# Power_supply.net
KiCad netlist of a schematic drawn in Altium Designer
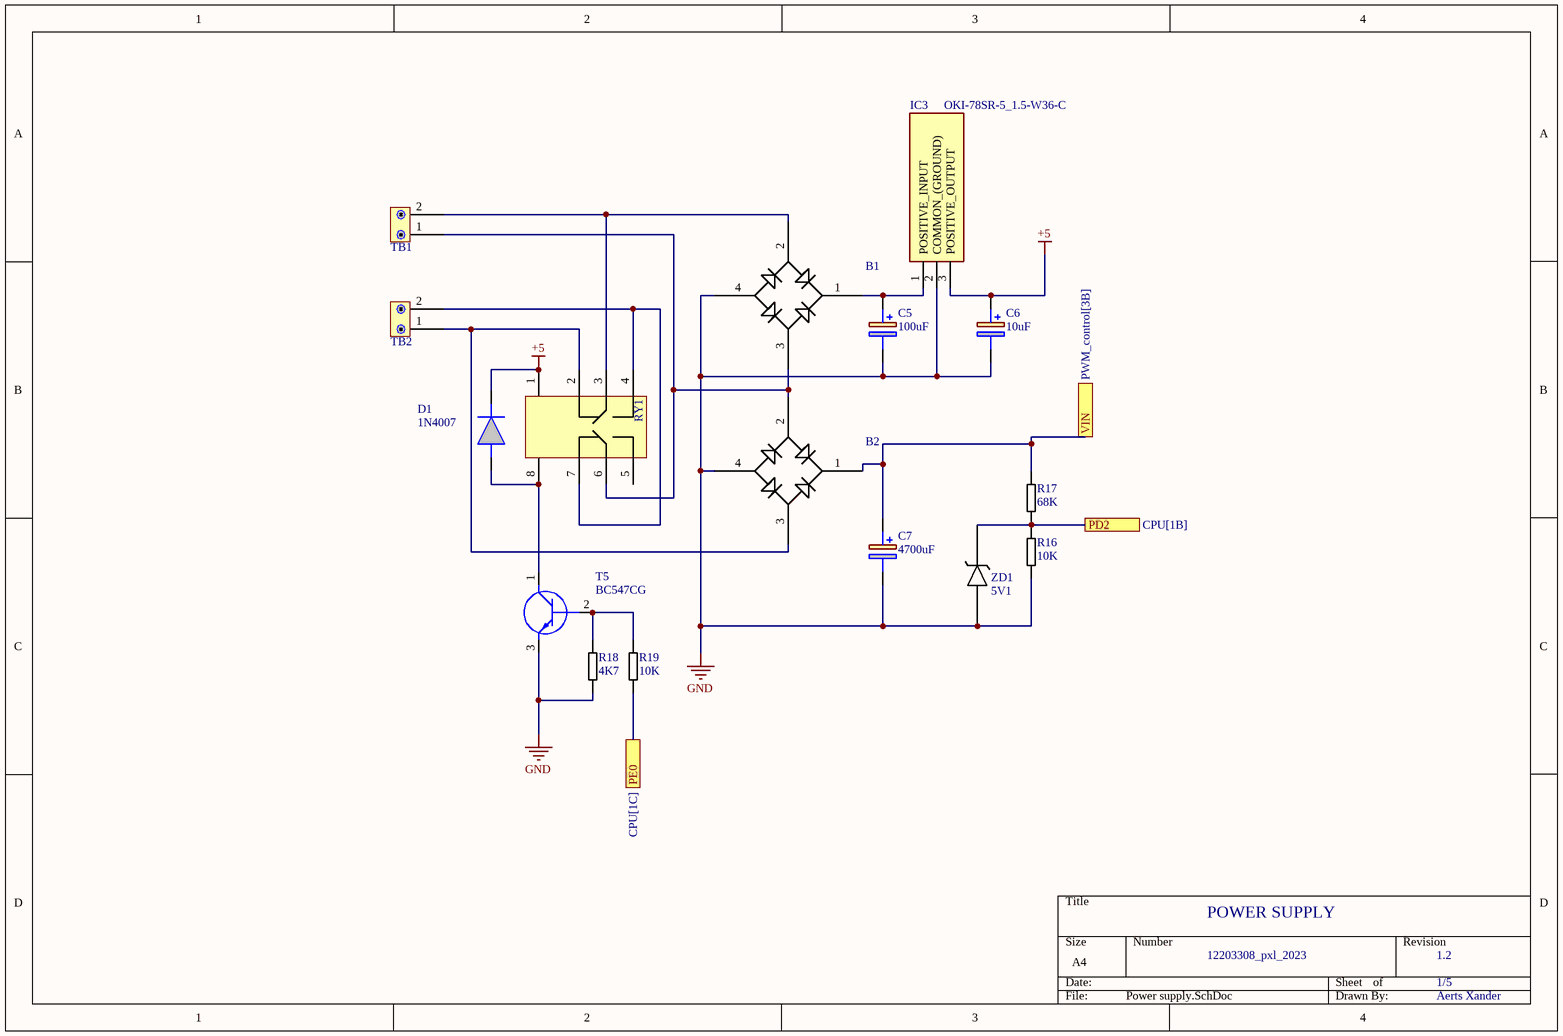
[diagram p0: Power supply.SchDoc]

(export (version "E")
  (design (tool "Eeschema 10.0.6"))
  (components
    (comp (ref "B1")
      (value "Bruggelijkrichter")
      (footprint "Bruggelijkrichter")
      (libsource (lib "soldeerstation") (part "Bruggelijkrichter"))
    )
    (comp (ref "B2")
      (value "Bruggelijkrichter")
      (footprint "Bruggelijkrichter")
      (libsource (lib "soldeerstation") (part "Bruggelijkrichter"))
    )
    (comp (ref "C5")
      (value "100uF")
      (footprint "100uf tht")
      (description "Aluminum Electrolytic Capacitors - Radial Leaded 50V 100uF 20%-MAL213631101E3")
      (fields
        (field (name "MOUSER PART NUMBER") "594-MAL213631101E3")
        (field (name "MANUFACTURER_PART_NUMBER") "MAL213631101E3")
      )
      (libsource (lib "soldeerstation") (part "100uf tht"))
    )
    (comp (ref "C6")
      (value "10uF")
      (footprint "10uF tht")
      (libsource (lib "soldeerstation") (part "10uF tht"))
    )
    (comp (ref "C7")
      (value "4700uF")
      (footprint "4700uf tht")
      (description "Cap Aluminum Lytic 4700uF 50V 20% (18 X 40mm) Radial 7.5mm 2800mA 2000h 85C Bulk")
      (fields
        (field (name "MOUSER PART NUMBER") "232-50PK4700MEFC18X4")
        (field (name "MANUFACTURER_PART_NUMBER") "50PK4700MEFC18X40")
      )
      (libsource (lib "soldeerstation") (part "4700uf tht"))
    )
    (comp (ref "D1")
      (value "1N4007")
      (footprint "1n4007")
      (fields (field (name "MOUSER PART NUMBER") "637-1N4007"))
      (libsource (lib "soldeerstation") (part "1N4007"))
    )
    (comp (ref "IC3")
      (value "OKI-78SR-5_1.5-W36-C")
      (footprint "OKI-78SR-5_1.5-W36-C")
      (description "Power Supply")
      (fields
        (field (name "MANUFACTURER_PART_NUMBER") "OKI-78SR-5/1.5-W36-C")
        (field (name "MOUSER PART NUMBER") "580-OKI78SR5/1.5W36C")
      )
      (libsource (lib "soldeerstation") (part "OKI-78SR-5_1.5-W36-C"))
    )
    (comp (ref "R16")
      (value "10K")
      (footprint "0805")
      (fields (field (name "MANUFACTURER") "Vishay Dale") (field (name "PART NUMBER") "CRCW08050000Z0EA"))
      (libsource (lib "soldeerstation") (part "resistor"))
    )
    (comp (ref "R17")
      (value "68K")
      (footprint "0805")
      (fields (field (name "MANUFACTURER") "Vishay Dale") (field (name "PART NUMBER") "CRCW08050000Z0EA"))
      (libsource (lib "soldeerstation") (part "resistor"))
    )
    (comp (ref "R18")
      (value "4K7")
      (footprint "0805")
      (fields (field (name "MANUFACTURER") "Vishay Dale") (field (name "PART NUMBER") "CRCW08050000Z0EA"))
      (libsource (lib "soldeerstation") (part "resistor"))
    )
    (comp (ref "R19")
      (value "10K")
      (footprint "0805")
      (fields (field (name "MANUFACTURER") "Vishay Dale") (field (name "PART NUMBER") "CRCW08050000Z0EA"))
      (libsource (lib "soldeerstation") (part "resistor"))
    )
    (comp (ref "RY1")
      (value "RT424005")
      (footprint "RT424005")
      (description "Relay or Contactor")
      (fields (field (name "MOUSER PART NUMBER") "655-RT424005"))
      (libsource (lib "soldeerstation") (part "RT424005"))
    )
    (comp (ref "T5")
      (value "BC547CG")
      (footprint "BC547CG")
      (description "Transistor BJT NPN")
      (fields (field (name "MOUSER PART NUMBER") "863-BC547CG"))
      (libsource (lib "soldeerstation") (part "BC547CG"))
    )
    (comp (ref "TB1")
      (value "2pin screw connector")
      (footprint "2pin screw connector")
      (libsource (lib "soldeerstation") (part "2pin screw connector"))
    )
    (comp (ref "TB2")
      (value "2pin screw connector")
      (footprint "2pin screw connector")
      (libsource (lib "soldeerstation") (part "2pin screw connector"))
    )
    (comp (ref "ZD1")
      (value "5V1")
      (footprint "1n4007")
      (libsource (lib "soldeerstation") (part "Zener 5.1 volt"))
    )
  )
  (nets
    (net (code "1") (name "+5") (class "Default")
      (node (ref "C6") (pin "1") (pinfunction "+_1") (pintype "passive"))
      (node (ref "D1") (pin "1") (pinfunction "K_1") (pintype "passive"))
      (node (ref "IC3") (pin "3") (pinfunction "POSITIVE_OUTPUT_3") (pintype "passive"))
      (node (ref "RY1") (pin "1") (pinfunction "A1_COIL_1") (pintype "passive"))
    )
    (net (code "2") (name "/PD2") (class "Default")
      (node (ref "R16") (pin "2") (pinfunction "2_2") (pintype "passive"))
      (node (ref "R17") (pin "1") (pinfunction "1_1") (pintype "passive"))
      (node (ref "ZD1") (pin "1") (pinfunction "28_1") (pintype "passive"))
    )
    (net (code "3") (name "/PE0") (class "Default")
      (node (ref "R19") (pin "2") (pinfunction "2_2") (pintype "passive"))
    )
    (net (code "4") (name "/VIN") (class "Default")
      (node (ref "B2") (pin "1") (pinfunction "13_1") (pintype "passive"))
      (node (ref "C7") (pin "1") (pinfunction "+_1") (pintype "passive"))
      (node (ref "R17") (pin "2") (pinfunction "2_2") (pintype "passive"))
    )
    (net (code "5") (name "GND") (class "Default")
      (node (ref "B1") (pin "4") (pinfunction "12_4") (pintype "passive"))
      (node (ref "B2") (pin "4") (pinfunction "12_4") (pintype "passive"))
      (node (ref "C5") (pin "2") (pinfunction "-_2") (pintype "passive"))
      (node (ref "C6") (pin "2") (pinfunction "-_2") (pintype "passive"))
      (node (ref "C7") (pin "2") (pinfunction "-_2") (pintype "passive"))
      (node (ref "IC3") (pin "2") (pinfunction "COMMON_(GROUND)_2") (pintype "passive"))
      (node (ref "R16") (pin "1") (pinfunction "1_1") (pintype "passive"))
      (node (ref "R18") (pin "2") (pinfunction "2_2") (pintype "passive"))
      (node (ref "T5") (pin "3") (pinfunction "E_3") (pintype "passive"))
      (node (ref "ZD1") (pin "2") (pinfunction "27_2") (pintype "passive"))
    )
    (net (code "6") (name "Net-(B1-13)") (class "Default")
      (node (ref "B1") (pin "1") (pinfunction "13_1") (pintype "passive"))
      (node (ref "C5") (pin "1") (pinfunction "+_1") (pintype "passive"))
      (node (ref "IC3") (pin "1") (pinfunction "POSITIVE_INPUT_1") (pintype "passive"))
    )
    (net (code "7") (name "Net-(B1-14)") (class "Default")
      (node (ref "B1") (pin "3") (pinfunction "14_3") (pintype "passive"))
      (node (ref "B2") (pin "2") (pinfunction "15_2") (pintype "passive"))
      (node (ref "RY1") (pin "6") (pinfunction "21_COM_6") (pintype "passive"))
      (node (ref "TB1") (pin "1") (pinfunction "29_1") (pintype "passive"))
    )
    (net (code "8") (name "Net-(B1-15)") (class "Default")
      (node (ref "B1") (pin "2") (pinfunction "15_2") (pintype "passive"))
      (node (ref "RY1") (pin "3") (pinfunction "11_COM_3") (pintype "passive"))
      (node (ref "TB1") (pin "2") (pinfunction "30_2") (pintype "passive"))
    )
    (net (code "9") (name "Net-(B2-14)") (class "Default")
      (node (ref "B2") (pin "3") (pinfunction "14_3") (pintype "passive"))
      (node (ref "RY1") (pin "2") (pinfunction "12_NC_2") (pintype "passive"))
      (node (ref "TB2") (pin "1") (pinfunction "29_1") (pintype "passive"))
    )
    (net (code "10") (name "Net-(D1-A)") (class "Default")
      (node (ref "D1") (pin "2") (pinfunction "A_2") (pintype "passive"))
      (node (ref "RY1") (pin "8") (pinfunction "A2_COIL_8") (pintype "passive"))
      (node (ref "T5") (pin "1") (pinfunction "C_1") (pintype "passive"))
    )
    (net (code "11") (name "Net-(RY1-14_NO)") (class "Default")
      (node (ref "RY1") (pin "4") (pinfunction "14_NO_4") (pintype "passive"))
      (node (ref "RY1") (pin "7") (pinfunction "22_NC_7") (pintype "passive"))
      (node (ref "TB2") (pin "2") (pinfunction "30_2") (pintype "passive"))
    )
    (net (code "12") (name "Net-(T5-B)") (class "Default")
      (node (ref "R18") (pin "1") (pinfunction "1_1") (pintype "passive"))
      (node (ref "R19") (pin "1") (pinfunction "1_1") (pintype "passive"))
      (node (ref "T5") (pin "2") (pinfunction "B_2") (pintype "passive"))
    )
    (net (code "13") (name "unconnected-(RY1-24_NO-Pad5)") (class "Default")
      (node (ref "RY1") (pin "5") (pinfunction "24_NO_5") (pintype "passive"))
    )
  )
)
